# IRAMX-drv-v3.net
KiCad netlist of a schematic drawn in EAGLE
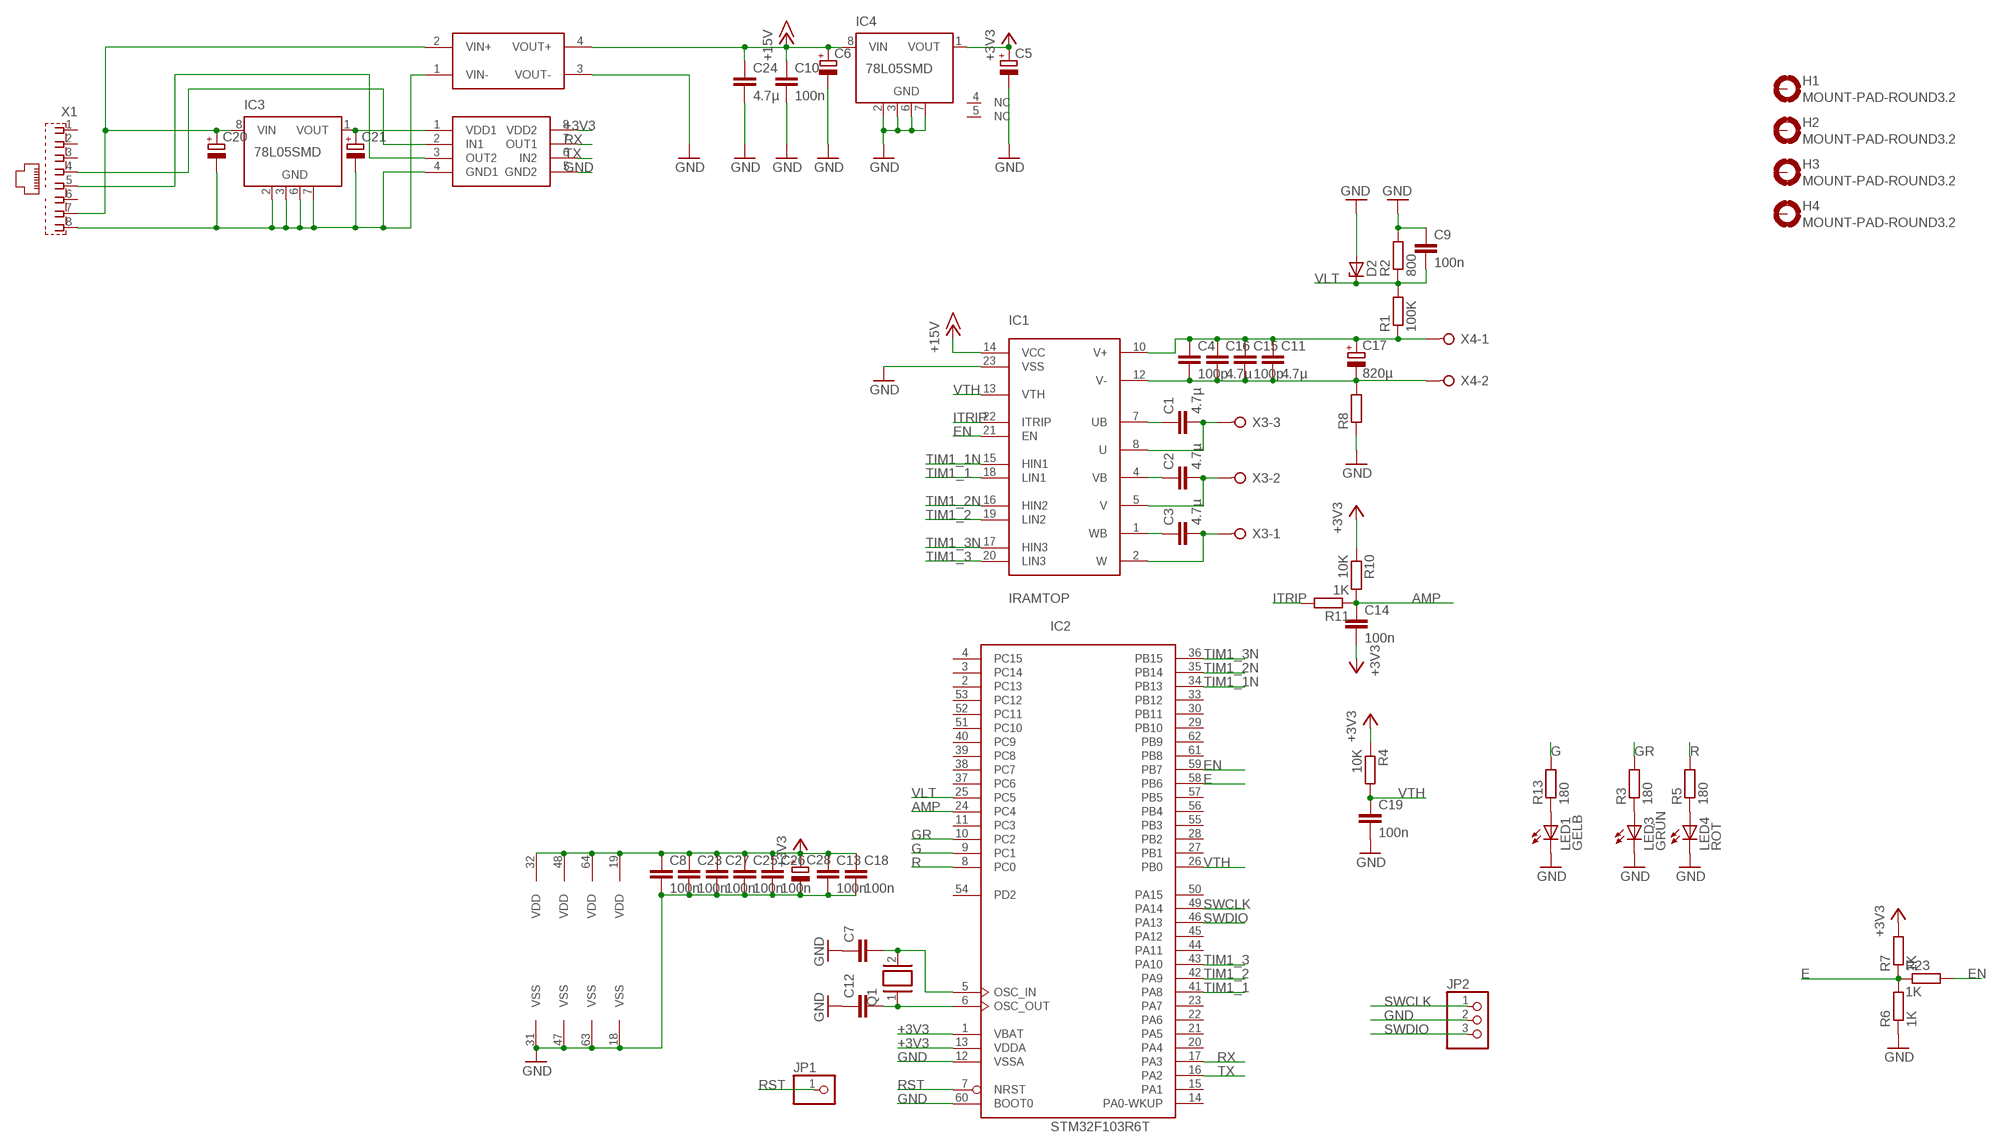
[diagram p0: schematic, sheet 1]

(export (version "E")
  (design (tool "Eeschema 10.0.6"))
  (components
    (comp (ref "C1")
      (value "4.7µ")
      (footprint "eagle-import:C0805K")
      (libsource (lib "eagle-import") (part "C-EUC0805K"))
    )
    (comp (ref "C2")
      (value "4.7µ")
      (footprint "eagle-import:C0805K")
      (libsource (lib "eagle-import") (part "C-EUC0805K"))
    )
    (comp (ref "C3")
      (value "4.7µ")
      (footprint "eagle-import:C0805K")
      (libsource (lib "eagle-import") (part "C-EUC0805K"))
    )
    (comp (ref "C4")
      (value "100p")
      (footprint "eagle-import:C1206K")
      (libsource (lib "eagle-import") (part "C-EUC1206K"))
    )
    (comp (ref "C5")
      (value "CPOL-EUA/3216-18R")
      (footprint "eagle-import:A_3216-18R")
      (libsource (lib "eagle-import") (part "CPOL-EUA/3216-18R"))
    )
    (comp (ref "C6")
      (value "CPOL-EUA/3216-18R")
      (footprint "eagle-import:A_3216-18R")
      (libsource (lib "eagle-import") (part "CPOL-EUA/3216-18R"))
    )
    (comp (ref "C7")
      (value "C-EUC0805")
      (footprint "eagle-import:C0805")
      (libsource (lib "eagle-import") (part "C-EUC0805"))
    )
    (comp (ref "C8")
      (value "100n")
      (footprint "eagle-import:C0805K")
      (libsource (lib "eagle-import") (part "C-EUC0805K"))
    )
    (comp (ref "C9")
      (value "100n")
      (footprint "eagle-import:C0805K")
      (libsource (lib "eagle-import") (part "C-EUC0805K"))
    )
    (comp (ref "C10")
      (value "100n")
      (footprint "eagle-import:C0805K")
      (libsource (lib "eagle-import") (part "C-EUC0805K"))
    )
    (comp (ref "C11")
      (value "4.7µ")
      (footprint "eagle-import:C0805K")
      (libsource (lib "eagle-import") (part "C-EUC0805K"))
    )
    (comp (ref "C12")
      (value "C-EUC0805")
      (footprint "eagle-import:C0805")
      (libsource (lib "eagle-import") (part "C-EUC0805"))
    )
    (comp (ref "C13")
      (value "100n")
      (footprint "eagle-import:C0805K")
      (libsource (lib "eagle-import") (part "C-EUC0805K"))
    )
    (comp (ref "C14")
      (value "100n")
      (footprint "eagle-import:C0805K")
      (libsource (lib "eagle-import") (part "C-EUC0805K"))
    )
    (comp (ref "C15")
      (value "100p")
      (footprint "eagle-import:C1206K")
      (libsource (lib "eagle-import") (part "C-EUC1206K"))
    )
    (comp (ref "C16")
      (value "4.7µ")
      (footprint "eagle-import:C0805K")
      (libsource (lib "eagle-import") (part "C-EUC0805K"))
    )
    (comp (ref "C17")
      (value "820µ")
      (footprint "eagle-import:EB35D")
      (libsource (lib "eagle-import") (part "CPOL-EUE10-35"))
    )
    (comp (ref "C18")
      (value "100n")
      (footprint "eagle-import:C0805K")
      (libsource (lib "eagle-import") (part "C-EUC0805K"))
    )
    (comp (ref "C19")
      (value "100n")
      (footprint "eagle-import:C0805K")
      (libsource (lib "eagle-import") (part "C-EUC0805K"))
    )
    (comp (ref "C20")
      (value "CPOL-EUA/3216-18R")
      (footprint "eagle-import:A_3216-18R")
      (libsource (lib "eagle-import") (part "CPOL-EUA/3216-18R"))
    )
    (comp (ref "C21")
      (value "CPOL-EUA/3216-18R")
      (footprint "eagle-import:A_3216-18R")
      (libsource (lib "eagle-import") (part "CPOL-EUA/3216-18R"))
    )
    (comp (ref "C23")
      (value "100n")
      (footprint "eagle-import:C0805K")
      (libsource (lib "eagle-import") (part "C-EUC0805K"))
    )
    (comp (ref "C24")
      (value "4.7µ")
      (footprint "eagle-import:C0805K")
      (libsource (lib "eagle-import") (part "C-EUC0805K"))
    )
    (comp (ref "C25")
      (value "100n")
      (footprint "eagle-import:C0805K")
      (libsource (lib "eagle-import") (part "C-EUC0805K"))
    )
    (comp (ref "C26")
      (value "100n")
      (footprint "eagle-import:C0805K")
      (libsource (lib "eagle-import") (part "C-EUC0805K"))
    )
    (comp (ref "C27")
      (value "100n")
      (footprint "eagle-import:C0805K")
      (libsource (lib "eagle-import") (part "C-EUC0805K"))
    )
    (comp (ref "C28")
      (value "CPOL-EUA/3216-18R")
      (footprint "eagle-import:A_3216-18R")
      (libsource (lib "eagle-import") (part "CPOL-EUA/3216-18R"))
    )
    (comp (ref "D2")
      (value "ZENER-DIODESOD80C")
      (footprint "eagle-import:SOD80C")
      (libsource (lib "eagle-import") (part "ZENER-DIODESOD80C"))
    )
    (comp (ref "H1")
      (value "MOUNT-PAD-ROUND3.2")
      (footprint "eagle-import:3,2-PAD")
      (libsource (lib "eagle-import") (part "MOUNT-PAD-ROUND3.2"))
    )
    (comp (ref "H2")
      (value "MOUNT-PAD-ROUND3.2")
      (footprint "eagle-import:3,2-PAD")
      (libsource (lib "eagle-import") (part "MOUNT-PAD-ROUND3.2"))
    )
    (comp (ref "H3")
      (value "MOUNT-PAD-ROUND3.2")
      (footprint "eagle-import:3,2-PAD")
      (libsource (lib "eagle-import") (part "MOUNT-PAD-ROUND3.2"))
    )
    (comp (ref "H4")
      (value "MOUNT-PAD-ROUND3.2")
      (footprint "eagle-import:3,2-PAD")
      (libsource (lib "eagle-import") (part "MOUNT-PAD-ROUND3.2"))
    )
    (comp (ref "IC1")
      (value "IRAMTOP")
      (footprint "eagle-import:SIP23_TOP")
      (libsource (lib "eagle-import") (part "IRAMTOP"))
    )
    (comp (ref "IC2")
      (value "STM32F103R6T")
      (footprint "eagle-import:LQFP64")
      (libsource (lib "eagle-import") (part "STM32F103RT6"))
    )
    (comp (ref "IC3")
      (value "78L05SMD")
      (footprint "eagle-import:SO08")
      (libsource (lib "eagle-import") (part "78LSMD05"))
    )
    (comp (ref "IC4")
      (value "78L05SMD")
      (footprint "eagle-import:SO08")
      (libsource (lib "eagle-import") (part "78LSMD05"))
    )
    (comp (ref "JP1")
      (value "PINHD-1X1")
      (footprint "eagle-import:1X01")
      (libsource (lib "eagle-import") (part "PINHD-1X1"))
    )
    (comp (ref "JP2")
      (value "PINHD-1X3")
      (footprint "eagle-import:1X03")
      (libsource (lib "eagle-import") (part "PINHD-1X3"))
    )
    (comp (ref "LED1")
      (value "GELB")
      (footprint "eagle-import:LED3MM")
      (libsource (lib "eagle-import") (part "LED3MM"))
    )
    (comp (ref "LED3")
      (value "GRÜN")
      (footprint "eagle-import:LED3MM")
      (libsource (lib "eagle-import") (part "LED3MM"))
    )
    (comp (ref "LED4")
      (value "ROT")
      (footprint "eagle-import:LED3MM")
      (libsource (lib "eagle-import") (part "LED3MM"))
    )
    (comp (ref "Q1")
      (value "XTAL/S")
      (footprint "eagle-import:QS")
      (libsource (lib "eagle-import") (part "XTAL/S"))
    )
    (comp (ref "R1")
      (value "100K")
      (footprint "eagle-import:R0805")
      (libsource (lib "eagle-import") (part "R-EU_R0805"))
    )
    (comp (ref "R2")
      (value "800")
      (footprint "eagle-import:R0805")
      (libsource (lib "eagle-import") (part "R-EU_R0805"))
    )
    (comp (ref "R3")
      (value "180")
      (footprint "eagle-import:R0805")
      (libsource (lib "eagle-import") (part "R-EU_R0805"))
    )
    (comp (ref "R4")
      (value "10K")
      (footprint "eagle-import:R0805")
      (libsource (lib "eagle-import") (part "R-EU_R0805"))
    )
    (comp (ref "R5")
      (value "180")
      (footprint "eagle-import:R0805")
      (libsource (lib "eagle-import") (part "R-EU_R0805"))
    )
    (comp (ref "R6")
      (value "1K")
      (footprint "eagle-import:R0805")
      (libsource (lib "eagle-import") (part "R-EU_R0805"))
    )
    (comp (ref "R7")
      (value "1K")
      (footprint "eagle-import:R0805")
      (libsource (lib "eagle-import") (part "R-EU_R0805"))
    )
    (comp (ref "R8")
      (value "R-EU_R0805")
      (footprint "eagle-import:R0805")
      (libsource (lib "eagle-import") (part "R-EU_R0805"))
    )
    (comp (ref "R10")
      (value "10K")
      (footprint "eagle-import:R0805")
      (libsource (lib "eagle-import") (part "R-EU_R0805"))
    )
    (comp (ref "R11")
      (value "1K")
      (footprint "eagle-import:R0805")
      (libsource (lib "eagle-import") (part "R-EU_R0805"))
    )
    (comp (ref "R13")
      (value "180")
      (footprint "eagle-import:R0805")
      (libsource (lib "eagle-import") (part "R-EU_R0805"))
    )
    (comp (ref "R23")
      (value "1K")
      (footprint "eagle-import:R0805")
      (libsource (lib "eagle-import") (part "R-EU_R0805"))
    )
    (comp (ref "U$1")
      (value "SI8621")
      (footprint "eagle-import:SOIC08")
      (libsource (lib "eagle-import") (part "SI8621"))
    )
    (comp (ref "U$2")
      (value "RO-XXXX")
      (footprint "eagle-import:SIP4")
      (libsource (lib "eagle-import") (part "RO-XXXX"))
    )
    (comp (ref "X1")
      (value "RJ45")
      (footprint "eagle-import:RJ45")
      (libsource (lib "eagle-import") (part "RJ45"))
    )
    (comp (ref "X3")
      (value "W237-03P")
      (footprint "eagle-import:W237-133")
      (libsource (lib "eagle-import") (part "W237-03P"))
    )
    (comp (ref "X4")
      (value "W237-02P")
      (footprint "eagle-import:W237-132")
      (libsource (lib "eagle-import") (part "W237-02P"))
    )
  )
  (nets
    (net (code "1") (name "+3V3") (class "Default")
      (node (ref "C13") (pin "1") (pinfunction "1_1") (pintype "passive"))
      (node (ref "C14") (pin "2") (pinfunction "2_2") (pintype "passive"))
      (node (ref "C18") (pin "1") (pinfunction "1_1") (pintype "passive"))
      (node (ref "C23") (pin "1") (pinfunction "1_1") (pintype "passive"))
      (node (ref "C25") (pin "1") (pinfunction "1_1") (pintype "passive"))
      (node (ref "C26") (pin "1") (pinfunction "1_1") (pintype "passive"))
      (node (ref "C27") (pin "1") (pinfunction "1_1") (pintype "passive"))
      (node (ref "C28") (pin "+") (pinfunction "+_+") (pintype "passive"))
      (node (ref "C5") (pin "+") (pinfunction "+_+") (pintype "passive"))
      (node (ref "C8") (pin "1") (pinfunction "1_1") (pintype "passive"))
      (node (ref "IC2") (pin "1") (pinfunction "VBAT_1") (pintype "power_in"))
      (node (ref "IC2") (pin "13") (pinfunction "VDDA_13") (pintype "power_in"))
      (node (ref "IC2") (pin "19") (pinfunction "VDD_19") (pintype "power_in"))
      (node (ref "IC2") (pin "32") (pinfunction "VDD_32") (pintype "power_in"))
      (node (ref "IC2") (pin "48") (pinfunction "VDD_48") (pintype "power_in"))
      (node (ref "IC2") (pin "64") (pinfunction "VDD_64") (pintype "power_in"))
      (node (ref "IC4") (pin "1") (pinfunction "VOUT_1") (pintype "output"))
      (node (ref "R10") (pin "1") (pinfunction "1_1") (pintype "passive"))
      (node (ref "R4") (pin "1") (pinfunction "1_1") (pintype "passive"))
      (node (ref "R7") (pin "2") (pinfunction "2_2") (pintype "passive"))
      (node (ref "U$1") (pin "8") (pinfunction "VDD2_8") (pintype "bidirectional"))
    )
    (net (code "2") (name "+15V") (class "Default")
      (node (ref "C10") (pin "1") (pinfunction "1_1") (pintype "passive"))
      (node (ref "C24") (pin "1") (pinfunction "1_1") (pintype "passive"))
      (node (ref "C6") (pin "+") (pinfunction "+_+") (pintype "passive"))
      (node (ref "IC1") (pin "14") (pinfunction "VCC_14") (pintype "bidirectional"))
      (node (ref "IC4") (pin "8") (pinfunction "VIN_8") (pintype "passive"))
      (node (ref "U$2") (pin "4") (pinfunction "VOUT+_4") (pintype "bidirectional"))
    )
    (net (code "3") (name "/AMP") (class "Default")
      (node (ref "C14") (pin "1") (pinfunction "1_1") (pintype "passive"))
      (node (ref "IC2") (pin "24") (pinfunction "PC4_24") (pintype "bidirectional"))
      (node (ref "R10") (pin "2") (pinfunction "2_2") (pintype "passive"))
      (node (ref "R11") (pin "1") (pinfunction "1_1") (pintype "passive"))
    )
    (net (code "4") (name "/E") (class "Default")
      (node (ref "IC2") (pin "58") (pinfunction "PB6_58") (pintype "bidirectional"))
      (node (ref "R23") (pin "1") (pinfunction "1_1") (pintype "passive"))
      (node (ref "R6") (pin "2") (pinfunction "2_2") (pintype "passive"))
      (node (ref "R7") (pin "1") (pinfunction "1_1") (pintype "passive"))
    )
    (net (code "5") (name "/EN") (class "Default")
      (node (ref "IC1") (pin "21") (pinfunction "EN_21") (pintype "bidirectional"))
      (node (ref "IC2") (pin "59") (pinfunction "PB7_59") (pintype "bidirectional"))
      (node (ref "R23") (pin "2") (pinfunction "2_2") (pintype "passive"))
    )
    (net (code "6") (name "/G") (class "Default")
      (node (ref "IC2") (pin "9") (pinfunction "PC1_9") (pintype "bidirectional"))
      (node (ref "R13") (pin "2") (pinfunction "2_2") (pintype "passive"))
    )
    (net (code "7") (name "/GR") (class "Default")
      (node (ref "IC2") (pin "10") (pinfunction "PC2_10") (pintype "bidirectional"))
      (node (ref "R3") (pin "2") (pinfunction "2_2") (pintype "passive"))
    )
    (net (code "8") (name "/ITRIP") (class "Default")
      (node (ref "IC1") (pin "22") (pinfunction "ITRIP_22") (pintype "bidirectional"))
      (node (ref "R11") (pin "2") (pinfunction "2_2") (pintype "passive"))
    )
    (net (code "9") (name "/R") (class "Default")
      (node (ref "IC2") (pin "8") (pinfunction "PC0_8") (pintype "bidirectional"))
      (node (ref "R5") (pin "2") (pinfunction "2_2") (pintype "passive"))
    )
    (net (code "10") (name "/RST") (class "Default")
      (node (ref "IC2") (pin "7") (pinfunction "NRST_7") (pintype "bidirectional"))
      (node (ref "JP1") (pin "1") (pinfunction "1_1") (pintype "passive"))
    )
    (net (code "11") (name "/RX") (class "Default")
      (node (ref "IC2") (pin "17") (pinfunction "PA3_17") (pintype "bidirectional"))
      (node (ref "U$1") (pin "7") (pinfunction "OUT1_7") (pintype "bidirectional"))
    )
    (net (code "12") (name "/SWCLK") (class "Default")
      (node (ref "IC2") (pin "49") (pinfunction "PA14_49") (pintype "bidirectional"))
      (node (ref "JP2") (pin "1") (pinfunction "1_1") (pintype "passive"))
    )
    (net (code "13") (name "/SWDIO") (class "Default")
      (node (ref "IC2") (pin "46") (pinfunction "PA13_46") (pintype "bidirectional"))
      (node (ref "JP2") (pin "3") (pinfunction "3_3") (pintype "passive"))
    )
    (net (code "14") (name "/TIM1_1") (class "Default")
      (node (ref "IC1") (pin "18") (pinfunction "LIN1_18") (pintype "bidirectional"))
      (node (ref "IC2") (pin "41") (pinfunction "PA8_41") (pintype "bidirectional"))
    )
    (net (code "15") (name "/TIM1_1N") (class "Default")
      (node (ref "IC1") (pin "15") (pinfunction "HIN1_15") (pintype "bidirectional"))
      (node (ref "IC2") (pin "34") (pinfunction "PB13_34") (pintype "bidirectional"))
    )
    (net (code "16") (name "/TIM1_2") (class "Default")
      (node (ref "IC1") (pin "19") (pinfunction "LIN2_19") (pintype "bidirectional"))
      (node (ref "IC2") (pin "42") (pinfunction "PA9_42") (pintype "bidirectional"))
    )
    (net (code "17") (name "/TIM1_2N") (class "Default")
      (node (ref "IC1") (pin "16") (pinfunction "HIN2_16") (pintype "bidirectional"))
      (node (ref "IC2") (pin "35") (pinfunction "PB14_35") (pintype "bidirectional"))
    )
    (net (code "18") (name "/TIM1_3") (class "Default")
      (node (ref "IC1") (pin "20") (pinfunction "LIN3_20") (pintype "bidirectional"))
      (node (ref "IC2") (pin "43") (pinfunction "PA10_43") (pintype "bidirectional"))
    )
    (net (code "19") (name "/TIM1_3N") (class "Default")
      (node (ref "IC1") (pin "17") (pinfunction "HIN3_17") (pintype "bidirectional"))
      (node (ref "IC2") (pin "36") (pinfunction "PB15_36") (pintype "bidirectional"))
    )
    (net (code "20") (name "/TX") (class "Default")
      (node (ref "IC2") (pin "16") (pinfunction "PA2_16") (pintype "bidirectional"))
      (node (ref "U$1") (pin "6") (pinfunction "IN2_6") (pintype "bidirectional"))
    )
    (net (code "21") (name "/VLT") (class "Default")
      (node (ref "C9") (pin "2") (pinfunction "2_2") (pintype "passive"))
      (node (ref "D2") (pin "C") (pinfunction "C_C") (pintype "passive"))
      (node (ref "IC2") (pin "25") (pinfunction "PC5_25") (pintype "bidirectional"))
      (node (ref "R1") (pin "2") (pinfunction "2_2") (pintype "passive"))
      (node (ref "R2") (pin "1") (pinfunction "1_1") (pintype "passive"))
    )
    (net (code "22") (name "/VTH") (class "Default")
      (node (ref "C19") (pin "1") (pinfunction "1_1") (pintype "passive"))
      (node (ref "IC1") (pin "13") (pinfunction "VTH_13") (pintype "bidirectional"))
      (node (ref "IC2") (pin "26") (pinfunction "PB0_26") (pintype "bidirectional"))
      (node (ref "R4") (pin "2") (pinfunction "2_2") (pintype "passive"))
    )
    (net (code "23") (name "GND") (class "Default")
      (node (ref "C10") (pin "2") (pinfunction "2_2") (pintype "passive"))
      (node (ref "C12") (pin "1") (pinfunction "1_1") (pintype "passive"))
      (node (ref "C13") (pin "2") (pinfunction "2_2") (pintype "passive"))
      (node (ref "C18") (pin "2") (pinfunction "2_2") (pintype "passive"))
      (node (ref "C19") (pin "2") (pinfunction "2_2") (pintype "passive"))
      (node (ref "C23") (pin "2") (pinfunction "2_2") (pintype "passive"))
      (node (ref "C24") (pin "2") (pinfunction "2_2") (pintype "passive"))
      (node (ref "C25") (pin "2") (pinfunction "2_2") (pintype "passive"))
      (node (ref "C26") (pin "2") (pinfunction "2_2") (pintype "passive"))
      (node (ref "C27") (pin "2") (pinfunction "2_2") (pintype "passive"))
      (node (ref "C28") (pin "-") (pinfunction "-_-") (pintype "passive"))
      (node (ref "C5") (pin "-") (pinfunction "-_-") (pintype "passive"))
      (node (ref "C6") (pin "-") (pinfunction "-_-") (pintype "passive"))
      (node (ref "C7") (pin "1") (pinfunction "1_1") (pintype "passive"))
      (node (ref "C8") (pin "2") (pinfunction "2_2") (pintype "passive"))
      (node (ref "C9") (pin "1") (pinfunction "1_1") (pintype "passive"))
      (node (ref "D2") (pin "A") (pinfunction "A_A") (pintype "passive"))
      (node (ref "IC1") (pin "23") (pinfunction "VSS_23") (pintype "bidirectional"))
      (node (ref "IC2") (pin "12") (pinfunction "VSSA_12") (pintype "power_in"))
      (node (ref "IC2") (pin "18") (pinfunction "VSS_18") (pintype "power_in"))
      (node (ref "IC2") (pin "31") (pinfunction "VSS_31") (pintype "power_in"))
      (node (ref "IC2") (pin "47") (pinfunction "VSS_47") (pintype "power_in"))
      (node (ref "IC2") (pin "60") (pinfunction "BOOT0_60") (pintype "input"))
      (node (ref "IC2") (pin "63") (pinfunction "VSS_63") (pintype "power_in"))
      (node (ref "IC4") (pin "2") (pinfunction "GND_2") (pintype "power_in"))
      (node (ref "IC4") (pin "3") (pinfunction "GND_3") (pintype "power_in"))
      (node (ref "IC4") (pin "6") (pinfunction "GND_6") (pintype "power_in"))
      (node (ref "IC4") (pin "7") (pinfunction "GND_7") (pintype "power_in"))
      (node (ref "JP2") (pin "2") (pinfunction "2_2") (pintype "passive"))
      (node (ref "LED1") (pin "K") (pinfunction "C_K") (pintype "passive"))
      (node (ref "LED3") (pin "K") (pinfunction "C_K") (pintype "passive"))
      (node (ref "LED4") (pin "K") (pinfunction "C_K") (pintype "passive"))
      (node (ref "R2") (pin "2") (pinfunction "2_2") (pintype "passive"))
      (node (ref "R6") (pin "1") (pinfunction "1_1") (pintype "passive"))
      (node (ref "R8") (pin "1") (pinfunction "1_1") (pintype "passive"))
      (node (ref "U$1") (pin "5") (pinfunction "GND2_5") (pintype "bidirectional"))
      (node (ref "U$2") (pin "3") (pinfunction "VOUT-_3") (pintype "bidirectional"))
    )
    (net (code "24") (name "Net-(IC1-U)") (class "Default")
      (node (ref "C1") (pin "2") (pinfunction "2_2") (pintype "passive"))
      (node (ref "IC1") (pin "8") (pinfunction "U_8") (pintype "bidirectional"))
      (node (ref "X3") (pin "3") (pinfunction "KL_3") (pintype "passive"))
    )
    (net (code "25") (name "Net-(IC1-UB)") (class "Default")
      (node (ref "C1") (pin "1") (pinfunction "1_1") (pintype "passive"))
      (node (ref "IC1") (pin "7") (pinfunction "UB_7") (pintype "bidirectional"))
    )
    (net (code "26") (name "Net-(IC1-V)") (class "Default")
      (node (ref "C2") (pin "2") (pinfunction "2_2") (pintype "passive"))
      (node (ref "IC1") (pin "5") (pinfunction "V_5") (pintype "bidirectional"))
      (node (ref "X3") (pin "2") (pinfunction "KL_2") (pintype "passive"))
    )
    (net (code "27") (name "Net-(IC1-V+)") (class "Default")
      (node (ref "C11") (pin "1") (pinfunction "1_1") (pintype "passive"))
      (node (ref "C15") (pin "1") (pinfunction "1_1") (pintype "passive"))
      (node (ref "C16") (pin "1") (pinfunction "1_1") (pintype "passive"))
      (node (ref "C17") (pin "+") (pinfunction "+_+") (pintype "passive"))
      (node (ref "C4") (pin "1") (pinfunction "1_1") (pintype "passive"))
      (node (ref "IC1") (pin "10") (pinfunction "V+_10") (pintype "bidirectional"))
      (node (ref "R1") (pin "1") (pinfunction "1_1") (pintype "passive"))
      (node (ref "X4") (pin "1") (pinfunction "KL_1") (pintype "passive"))
    )
    (net (code "28") (name "Net-(IC1-V-)") (class "Default")
      (node (ref "C11") (pin "2") (pinfunction "2_2") (pintype "passive"))
      (node (ref "C15") (pin "2") (pinfunction "2_2") (pintype "passive"))
      (node (ref "C16") (pin "2") (pinfunction "2_2") (pintype "passive"))
      (node (ref "C17") (pin "-") (pinfunction "-_-") (pintype "passive"))
      (node (ref "C4") (pin "2") (pinfunction "2_2") (pintype "passive"))
      (node (ref "IC1") (pin "12") (pinfunction "V-_12") (pintype "bidirectional"))
      (node (ref "R8") (pin "2") (pinfunction "2_2") (pintype "passive"))
      (node (ref "X4") (pin "2") (pinfunction "KL_2") (pintype "passive"))
    )
    (net (code "29") (name "Net-(IC1-VB)") (class "Default")
      (node (ref "C2") (pin "1") (pinfunction "1_1") (pintype "passive"))
      (node (ref "IC1") (pin "4") (pinfunction "VB_4") (pintype "bidirectional"))
    )
    (net (code "30") (name "Net-(IC1-W)") (class "Default")
      (node (ref "C3") (pin "2") (pinfunction "2_2") (pintype "passive"))
      (node (ref "IC1") (pin "2") (pinfunction "W_2") (pintype "bidirectional"))
      (node (ref "X3") (pin "1") (pinfunction "KL_1") (pintype "passive"))
    )
    (net (code "31") (name "Net-(IC1-WB)") (class "Default")
      (node (ref "C3") (pin "1") (pinfunction "1_1") (pintype "passive"))
      (node (ref "IC1") (pin "1") (pinfunction "WB_1") (pintype "bidirectional"))
    )
    (net (code "32") (name "Net-(IC2A-OSC_IN)") (class "Default")
      (node (ref "C7") (pin "2") (pinfunction "2_2") (pintype "passive"))
      (node (ref "IC2") (pin "5") (pinfunction "OSC_IN_5") (pintype "bidirectional"))
      (node (ref "Q1") (pin "2") (pinfunction "2_2") (pintype "passive"))
    )
    (net (code "33") (name "Net-(IC2A-OSC_OUT)") (class "Default")
      (node (ref "C12") (pin "2") (pinfunction "2_2") (pintype "passive"))
      (node (ref "IC2") (pin "6") (pinfunction "OSC_OUT_6") (pintype "bidirectional"))
      (node (ref "Q1") (pin "1") (pinfunction "1_1") (pintype "passive"))
    )
    (net (code "34") (name "Net-(IC3A-VIN)") (class "Default")
      (node (ref "C20") (pin "+") (pinfunction "+_+") (pintype "passive"))
      (node (ref "IC3") (pin "8") (pinfunction "VIN_8") (pintype "passive"))
      (node (ref "U$2") (pin "2") (pinfunction "VIN+_2") (pintype "bidirectional"))
      (node (ref "X1") (pin "7") (pinfunction "7_7") (pintype "passive"))
    )
    (net (code "35") (name "Net-(IC3A-VOUT)") (class "Default")
      (node (ref "C21") (pin "+") (pinfunction "+_+") (pintype "passive"))
      (node (ref "IC3") (pin "1") (pinfunction "VOUT_1") (pintype "output"))
      (node (ref "U$1") (pin "1") (pinfunction "VDD1_1") (pintype "bidirectional"))
    )
    (net (code "36") (name "Net-(LED1-PadA)") (class "Default")
      (node (ref "LED1") (pin "A") (pinfunction "A_A") (pintype "passive"))
      (node (ref "R13") (pin "1") (pinfunction "1_1") (pintype "passive"))
    )
    (net (code "37") (name "Net-(LED3-PadA)") (class "Default")
      (node (ref "LED3") (pin "A") (pinfunction "A_A") (pintype "passive"))
      (node (ref "R3") (pin "1") (pinfunction "1_1") (pintype "passive"))
    )
    (net (code "38") (name "Net-(LED4-PadA)") (class "Default")
      (node (ref "LED4") (pin "A") (pinfunction "A_A") (pintype "passive"))
      (node (ref "R5") (pin "1") (pinfunction "1_1") (pintype "passive"))
    )
    (net (code "39") (name "Net-(U$1-GND1)") (class "Default")
      (node (ref "C20") (pin "-") (pinfunction "-_-") (pintype "passive"))
      (node (ref "C21") (pin "-") (pinfunction "-_-") (pintype "passive"))
      (node (ref "IC3") (pin "2") (pinfunction "GND_2") (pintype "power_in"))
      (node (ref "IC3") (pin "3") (pinfunction "GND_3") (pintype "power_in"))
      (node (ref "IC3") (pin "6") (pinfunction "GND_6") (pintype "power_in"))
      (node (ref "IC3") (pin "7") (pinfunction "GND_7") (pintype "power_in"))
      (node (ref "U$1") (pin "4") (pinfunction "GND1_4") (pintype "bidirectional"))
      (node (ref "U$2") (pin "1") (pinfunction "VIN-_1") (pintype "bidirectional"))
      (node (ref "X1") (pin "8") (pinfunction "8_8") (pintype "passive"))
    )
    (net (code "40") (name "Net-(U$1-IN1)") (class "Default")
      (node (ref "U$1") (pin "2") (pinfunction "IN1_2") (pintype "bidirectional"))
      (node (ref "X1") (pin "4") (pinfunction "4_4") (pintype "passive"))
    )
    (net (code "41") (name "Net-(U$1-OUT2)") (class "Default")
      (node (ref "U$1") (pin "3") (pinfunction "OUT2_3") (pintype "bidirectional"))
      (node (ref "X1") (pin "5") (pinfunction "5_5") (pintype "passive"))
    )
    (net (code "42") (name "unconnected-(H1-MOUNT-PadB3,2)") (class "Default")
      (node (ref "H1") (pin "B3,2") (pinfunction "MOUNT_B3,2") (pintype "passive"))
    )
    (net (code "43") (name "unconnected-(H2-MOUNT-PadB3,2)") (class "Default")
      (node (ref "H2") (pin "B3,2") (pinfunction "MOUNT_B3,2") (pintype "passive"))
    )
    (net (code "44") (name "unconnected-(H3-MOUNT-PadB3,2)") (class "Default")
      (node (ref "H3") (pin "B3,2") (pinfunction "MOUNT_B3,2") (pintype "passive"))
    )
    (net (code "45") (name "unconnected-(H4-MOUNT-PadB3,2)") (class "Default")
      (node (ref "H4") (pin "B3,2") (pinfunction "MOUNT_B3,2") (pintype "passive"))
    )
    (net (code "46") (name "unconnected-(IC2A-PA0-WKUP-Pad14)") (class "Default")
      (node (ref "IC2") (pin "14") (pinfunction "PA0-WKUP_14") (pintype "bidirectional"))
    )
    (net (code "47") (name "unconnected-(IC2A-PA1-Pad15)") (class "Default")
      (node (ref "IC2") (pin "15") (pinfunction "PA1_15") (pintype "bidirectional"))
    )
    (net (code "48") (name "unconnected-(IC2A-PA4-Pad20)") (class "Default")
      (node (ref "IC2") (pin "20") (pinfunction "PA4_20") (pintype "bidirectional"))
    )
    (net (code "49") (name "unconnected-(IC2A-PA5-Pad21)") (class "Default")
      (node (ref "IC2") (pin "21") (pinfunction "PA5_21") (pintype "bidirectional"))
    )
    (net (code "50") (name "unconnected-(IC2A-PA6-Pad22)") (class "Default")
      (node (ref "IC2") (pin "22") (pinfunction "PA6_22") (pintype "bidirectional"))
    )
    (net (code "51") (name "unconnected-(IC2A-PA7-Pad23)") (class "Default")
      (node (ref "IC2") (pin "23") (pinfunction "PA7_23") (pintype "bidirectional"))
    )
    (net (code "52") (name "unconnected-(IC2A-PA11-Pad44)") (class "Default")
      (node (ref "IC2") (pin "44") (pinfunction "PA11_44") (pintype "bidirectional"))
    )
    (net (code "53") (name "unconnected-(IC2A-PA12-Pad45)") (class "Default")
      (node (ref "IC2") (pin "45") (pinfunction "PA12_45") (pintype "bidirectional"))
    )
    (net (code "54") (name "unconnected-(IC2A-PA15-Pad50)") (class "Default")
      (node (ref "IC2") (pin "50") (pinfunction "PA15_50") (pintype "bidirectional"))
    )
    (net (code "55") (name "unconnected-(IC2A-PB1-Pad27)") (class "Default")
      (node (ref "IC2") (pin "27") (pinfunction "PB1_27") (pintype "bidirectional"))
    )
    (net (code "56") (name "unconnected-(IC2A-PB2-Pad28)") (class "Default")
      (node (ref "IC2") (pin "28") (pinfunction "PB2_28") (pintype "bidirectional"))
    )
    (net (code "57") (name "unconnected-(IC2A-PB3-Pad55)") (class "Default")
      (node (ref "IC2") (pin "55") (pinfunction "PB3_55") (pintype "bidirectional"))
    )
    (net (code "58") (name "unconnected-(IC2A-PB4-Pad56)") (class "Default")
      (node (ref "IC2") (pin "56") (pinfunction "PB4_56") (pintype "bidirectional"))
    )
    (net (code "59") (name "unconnected-(IC2A-PB5-Pad57)") (class "Default")
      (node (ref "IC2") (pin "57") (pinfunction "PB5_57") (pintype "bidirectional"))
    )
    (net (code "60") (name "unconnected-(IC2A-PB8-Pad61)") (class "Default")
      (node (ref "IC2") (pin "61") (pinfunction "PB8_61") (pintype "bidirectional"))
    )
    (net (code "61") (name "unconnected-(IC2A-PB9-Pad62)") (class "Default")
      (node (ref "IC2") (pin "62") (pinfunction "PB9_62") (pintype "bidirectional"))
    )
    (net (code "62") (name "unconnected-(IC2A-PB10-Pad29)") (class "Default")
      (node (ref "IC2") (pin "29") (pinfunction "PB10_29") (pintype "bidirectional"))
    )
    (net (code "63") (name "unconnected-(IC2A-PB11-Pad30)") (class "Default")
      (node (ref "IC2") (pin "30") (pinfunction "PB11_30") (pintype "bidirectional"))
    )
    (net (code "64") (name "unconnected-(IC2A-PB12-Pad33)") (class "Default")
      (node (ref "IC2") (pin "33") (pinfunction "PB12_33") (pintype "bidirectional"))
    )
    (net (code "65") (name "unconnected-(IC2A-PC3-Pad11)") (class "Default")
      (node (ref "IC2") (pin "11") (pinfunction "PC3_11") (pintype "bidirectional"))
    )
    (net (code "66") (name "unconnected-(IC2A-PC6-Pad37)") (class "Default")
      (node (ref "IC2") (pin "37") (pinfunction "PC6_37") (pintype "bidirectional"))
    )
    (net (code "67") (name "unconnected-(IC2A-PC7-Pad38)") (class "Default")
      (node (ref "IC2") (pin "38") (pinfunction "PC7_38") (pintype "bidirectional"))
    )
    (net (code "68") (name "unconnected-(IC2A-PC8-Pad39)") (class "Default")
      (node (ref "IC2") (pin "39") (pinfunction "PC8_39") (pintype "bidirectional"))
    )
    (net (code "69") (name "unconnected-(IC2A-PC9-Pad40)") (class "Default")
      (node (ref "IC2") (pin "40") (pinfunction "PC9_40") (pintype "bidirectional"))
    )
    (net (code "70") (name "unconnected-(IC2A-PC10-Pad51)") (class "Default")
      (node (ref "IC2") (pin "51") (pinfunction "PC10_51") (pintype "bidirectional"))
    )
    (net (code "71") (name "unconnected-(IC2A-PC11-Pad52)") (class "Default")
      (node (ref "IC2") (pin "52") (pinfunction "PC11_52") (pintype "bidirectional"))
    )
    (net (code "72") (name "unconnected-(IC2A-PC12-Pad53)") (class "Default")
      (node (ref "IC2") (pin "53") (pinfunction "PC12_53") (pintype "bidirectional"))
    )
    (net (code "73") (name "unconnected-(IC2A-PC13-Pad2)") (class "Default")
      (node (ref "IC2") (pin "2") (pinfunction "PC13_2") (pintype "bidirectional"))
    )
    (net (code "74") (name "unconnected-(IC2A-PC14-Pad3)") (class "Default")
      (node (ref "IC2") (pin "3") (pinfunction "PC14_3") (pintype "bidirectional"))
    )
    (net (code "75") (name "unconnected-(IC2A-PC15-Pad4)") (class "Default")
      (node (ref "IC2") (pin "4") (pinfunction "PC15_4") (pintype "bidirectional"))
    )
    (net (code "76") (name "unconnected-(IC2A-PD2-Pad54)") (class "Default")
      (node (ref "IC2") (pin "54") (pinfunction "PD2_54") (pintype "bidirectional"))
    )
    (net (code "77") (name "unconnected-(IC4B-NC-Pad4)") (class "Default")
      (node (ref "IC4") (pin "4") (pinfunction "NC_4") (pintype "no_connect"))
    )
    (net (code "78") (name "unconnected-(IC4C-NC-Pad5)") (class "Default")
      (node (ref "IC4") (pin "5") (pinfunction "NC_5") (pintype "no_connect"))
    )
    (net (code "79") (name "unconnected-(X1-Pad1)") (class "Default")
      (node (ref "X1") (pin "1") (pinfunction "1_1") (pintype "passive"))
    )
    (net (code "80") (name "unconnected-(X1-Pad2)") (class "Default")
      (node (ref "X1") (pin "2") (pinfunction "2_2") (pintype "passive"))
    )
    (net (code "81") (name "unconnected-(X1-Pad3)") (class "Default")
      (node (ref "X1") (pin "3") (pinfunction "3_3") (pintype "passive"))
    )
    (net (code "82") (name "unconnected-(X1-Pad6)") (class "Default")
      (node (ref "X1") (pin "6") (pinfunction "6_6") (pintype "passive"))
    )
  )
)
